# Antenna_analyzer_shield.net
KiCad netlist of a schematic drawn in EAGLE
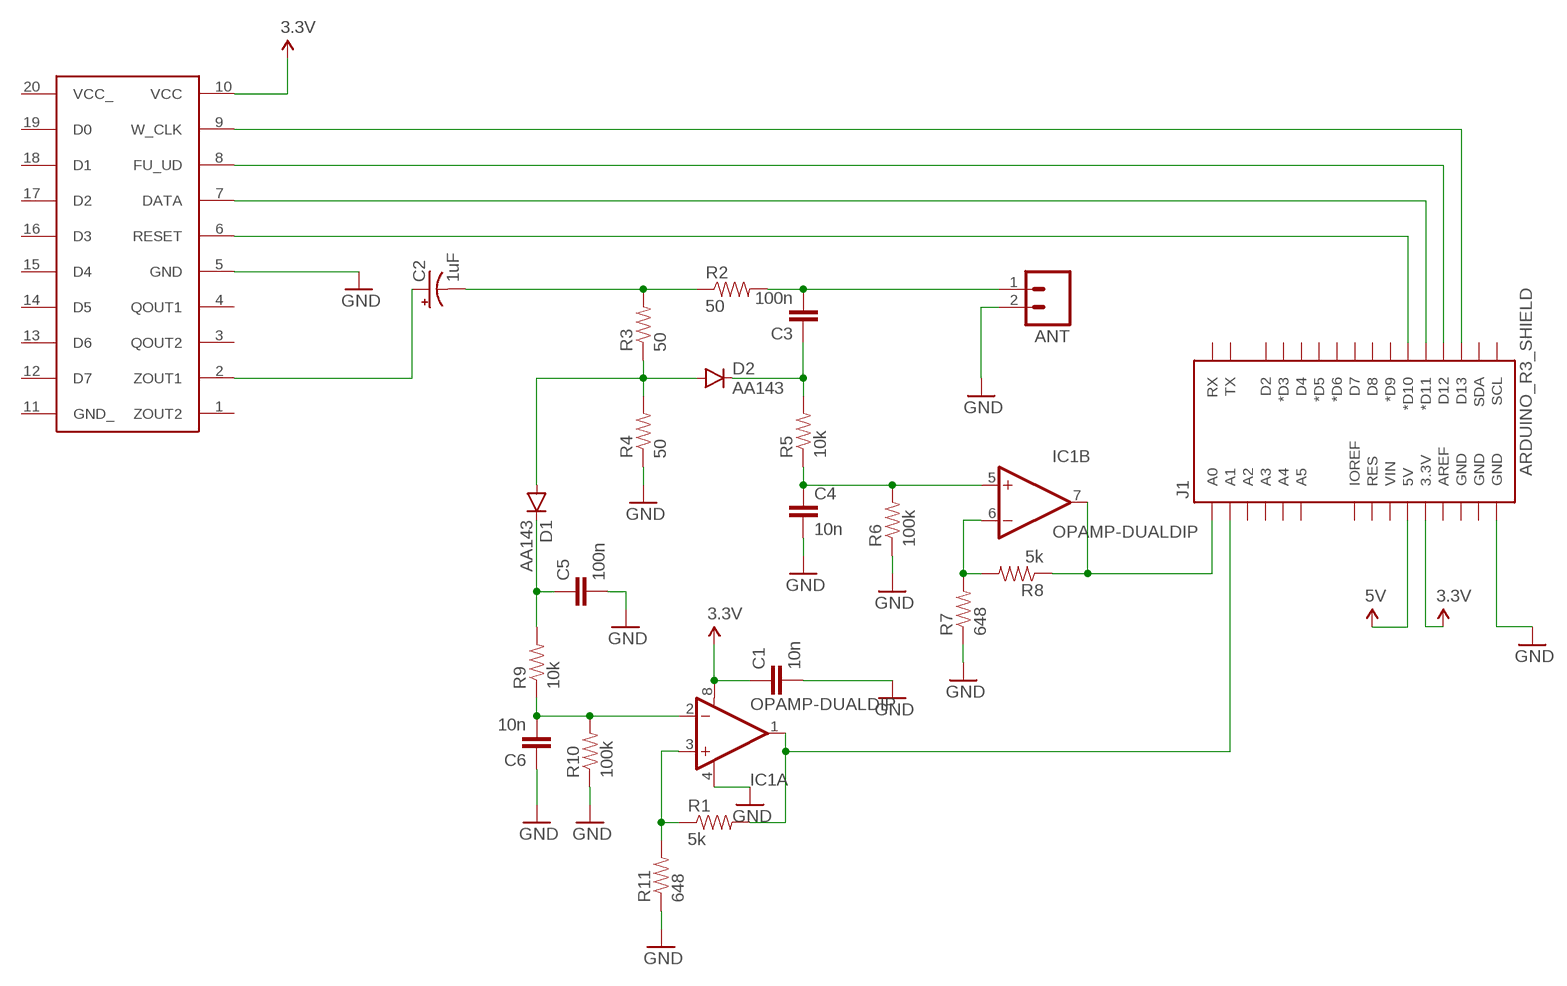
[diagram p0: schematic, sheet 1]

(export (version "E")
  (design (tool "Eeschema 10.0.6"))
  (components
    (comp (ref "ANT")
      (value "M023.5MM")
      (footprint "eagle-import:SCREWTERMINAL-3.5MM-2")
      (libsource (lib "eagle-import") (part "M023.5MM"))
    )
    (comp (ref "C1")
      (value "10n")
      (footprint "eagle-import:CAP-PTH-SMALL2")
      (libsource (lib "eagle-import") (part "CAPPTH2"))
    )
    (comp (ref "C2")
      (value "1uF")
      (footprint "eagle-import:CPOL-RADIAL-10UF-25V")
      (libsource (lib "eagle-import") (part "CAP_POLPTH2"))
    )
    (comp (ref "C3")
      (value "100n")
      (footprint "eagle-import:CAP-PTH-SMALL2")
      (libsource (lib "eagle-import") (part "CAPPTH2"))
    )
    (comp (ref "C4")
      (value "10n")
      (footprint "eagle-import:CAP-PTH-SMALL2")
      (libsource (lib "eagle-import") (part "CAPPTH2"))
    )
    (comp (ref "C5")
      (value "100n")
      (footprint "eagle-import:CAP-PTH-SMALL2")
      (libsource (lib "eagle-import") (part "CAPPTH2"))
    )
    (comp (ref "C6")
      (value "10n")
      (footprint "eagle-import:CAP-PTH-SMALL2")
      (libsource (lib "eagle-import") (part "CAPPTH2"))
    )
    (comp (ref "D1")
      (value "AA143")
      (footprint "eagle-import:DIODE-1N4001")
      (libsource (lib "eagle-import") (part "DIODEPTH"))
    )
    (comp (ref "D2")
      (value "AA143")
      (footprint "eagle-import:DIODE-1N4001")
      (libsource (lib "eagle-import") (part "DIODEPTH"))
    )
    (comp (ref "IC1")
      (value "OPAMP-DUALDIP")
      (footprint "eagle-import:DIP08")
      (libsource (lib "eagle-import") (part "OPAMP-DUALDIP"))
    )
    (comp (ref "J1")
      (value "ARDUINO_R3_SHIELD")
      (footprint "eagle-import:UNO_R3_SHIELD")
      (libsource (lib "eagle-import") (part "ARDUINO_R3_SHIELD"))
    )
    (comp (ref "R1")
      (value "5k")
      (footprint "eagle-import:AXIAL-0.4")
      (libsource (lib "eagle-import") (part "RESISTORPTH-1/4W"))
    )
    (comp (ref "R2")
      (value "50")
      (footprint "eagle-import:AXIAL-0.4")
      (libsource (lib "eagle-import") (part "RESISTORPTH-1/4W"))
    )
    (comp (ref "R3")
      (value "50")
      (footprint "eagle-import:AXIAL-0.4")
      (libsource (lib "eagle-import") (part "RESISTORPTH-1/4W"))
    )
    (comp (ref "R4")
      (value "50")
      (footprint "eagle-import:AXIAL-0.4")
      (libsource (lib "eagle-import") (part "RESISTORPTH-1/4W"))
    )
    (comp (ref "R5")
      (value "10k")
      (footprint "eagle-import:AXIAL-0.4")
      (libsource (lib "eagle-import") (part "RESISTORPTH-1/4W"))
    )
    (comp (ref "R6")
      (value "100k")
      (footprint "eagle-import:AXIAL-0.4")
      (libsource (lib "eagle-import") (part "RESISTORPTH-1/4W"))
    )
    (comp (ref "R7")
      (value "648")
      (footprint "eagle-import:AXIAL-0.4")
      (libsource (lib "eagle-import") (part "RESISTORPTH-1/4W"))
    )
    (comp (ref "R8")
      (value "5k")
      (footprint "eagle-import:AXIAL-0.4")
      (libsource (lib "eagle-import") (part "RESISTORPTH-1/4W"))
    )
    (comp (ref "R9")
      (value "10k")
      (footprint "eagle-import:AXIAL-0.4")
      (libsource (lib "eagle-import") (part "RESISTORPTH-1/4W"))
    )
    (comp (ref "R10")
      (value "100k")
      (footprint "eagle-import:AXIAL-0.4")
      (libsource (lib "eagle-import") (part "RESISTORPTH-1/4W"))
    )
    (comp (ref "R11")
      (value "648")
      (footprint "eagle-import:AXIAL-0.4")
      (libsource (lib "eagle-import") (part "RESISTORPTH-1/4W"))
    )
    (comp (ref "U$1")
      (value "DDS")
      (footprint "eagle-import:1X10_NO_SILK")
      (libsource (lib "eagle-import") (part "DDS"))
    )
  )
  (nets
    (net (code "1") (name "3.3V") (class "Default")
      (node (ref "C1") (pin "1") (pinfunction "1_1") (pintype "passive"))
      (node (ref "IC1") (pin "8") (pinfunction "V+_8") (pintype "power_in"))
      (node (ref "J1") (pin "3.3V") (pinfunction "3.3V_3.3V") (pintype "bidirectional"))
      (node (ref "J1") (pin "5V") (pinfunction "5V_5V") (pintype "bidirectional"))
      (node (ref "U$1") (pin "10") (pinfunction "VCC_10") (pintype "bidirectional"))
    )
    (net (code "2") (name "GND") (class "Default")
      (node (ref "ANT") (pin "2") (pinfunction "2_2") (pintype "passive"))
      (node (ref "C1") (pin "2") (pinfunction "2_2") (pintype "passive"))
      (node (ref "C4") (pin "2") (pinfunction "2_2") (pintype "passive"))
      (node (ref "C5") (pin "2") (pinfunction "2_2") (pintype "passive"))
      (node (ref "C6") (pin "1") (pinfunction "1_1") (pintype "passive"))
      (node (ref "IC1") (pin "4") (pinfunction "V-_4") (pintype "power_in"))
      (node (ref "J1") (pin "GND@0") (pinfunction "GND_GND@0") (pintype "bidirectional"))
      (node (ref "R10") (pin "P$1") (pinfunction "1_P$1") (pintype "passive"))
      (node (ref "R11") (pin "P$1") (pinfunction "1_P$1") (pintype "passive"))
      (node (ref "R4") (pin "P$1") (pinfunction "1_P$1") (pintype "passive"))
      (node (ref "R6") (pin "P$1") (pinfunction "1_P$1") (pintype "passive"))
      (node (ref "R7") (pin "P$1") (pinfunction "1_P$1") (pintype "passive"))
      (node (ref "U$1") (pin "5") (pinfunction "GND_5") (pintype "bidirectional"))
    )
    (net (code "3") (name "Net-(C2-+)") (class "Default")
      (node (ref "C2") (pin "1") (pinfunction "+_1") (pintype "passive"))
      (node (ref "U$1") (pin "2") (pinfunction "ZOUT1_2") (pintype "bidirectional"))
    )
    (net (code "4") (name "Net-(C2--)") (class "Default")
      (node (ref "C2") (pin "2") (pinfunction "-_2") (pintype "passive"))
      (node (ref "R2") (pin "P$1") (pinfunction "1_P$1") (pintype "passive"))
      (node (ref "R3") (pin "P$2") (pinfunction "2_P$2") (pintype "passive"))
    )
    (net (code "5") (name "Net-(IC1A-+IN)") (class "Default")
      (node (ref "IC1") (pin "3") (pinfunction "+IN_3") (pintype "input"))
      (node (ref "R1") (pin "P$1") (pinfunction "1_P$1") (pintype "passive"))
      (node (ref "R11") (pin "P$2") (pinfunction "2_P$2") (pintype "passive"))
    )
    (net (code "6") (name "Net-(IC1A--IN)") (class "Default")
      (node (ref "C6") (pin "2") (pinfunction "2_2") (pintype "passive"))
      (node (ref "IC1") (pin "2") (pinfunction "-IN_2") (pintype "input"))
      (node (ref "R10") (pin "P$2") (pinfunction "2_P$2") (pintype "passive"))
      (node (ref "R9") (pin "P$1") (pinfunction "1_P$1") (pintype "passive"))
    )
    (net (code "7") (name "Net-(IC1A-OUT)") (class "Default")
      (node (ref "IC1") (pin "1") (pinfunction "OUT_1") (pintype "output"))
      (node (ref "J1") (pin "A1") (pinfunction "A1_A1") (pintype "bidirectional"))
      (node (ref "R1") (pin "P$2") (pinfunction "2_P$2") (pintype "passive"))
    )
    (net (code "8") (name "Net-(IC1B-+IN)") (class "Default")
      (node (ref "C4") (pin "1") (pinfunction "1_1") (pintype "passive"))
      (node (ref "IC1") (pin "5") (pinfunction "+IN_5") (pintype "input"))
      (node (ref "R5") (pin "P$1") (pinfunction "1_P$1") (pintype "passive"))
      (node (ref "R6") (pin "P$2") (pinfunction "2_P$2") (pintype "passive"))
    )
    (net (code "9") (name "Net-(IC1B--IN)") (class "Default")
      (node (ref "IC1") (pin "6") (pinfunction "-IN_6") (pintype "input"))
      (node (ref "R7") (pin "P$2") (pinfunction "2_P$2") (pintype "passive"))
      (node (ref "R8") (pin "P$2") (pinfunction "2_P$2") (pintype "passive"))
    )
    (net (code "10") (name "Net-(IC1B-OUT)") (class "Default")
      (node (ref "IC1") (pin "7") (pinfunction "OUT_7") (pintype "output"))
      (node (ref "J1") (pin "A0") (pinfunction "A0_A0") (pintype "bidirectional"))
      (node (ref "R8") (pin "P$1") (pinfunction "1_P$1") (pintype "passive"))
    )
    (net (code "11") (name "Net-(J1-*D10)") (class "Default")
      (node (ref "J1") (pin "D10") (pinfunction "*D10_D10") (pintype "bidirectional"))
      (node (ref "U$1") (pin "6") (pinfunction "RESET_6") (pintype "bidirectional"))
    )
    (net (code "12") (name "Net-(J1-*D11)") (class "Default")
      (node (ref "J1") (pin "D11") (pinfunction "*D11_D11") (pintype "bidirectional"))
      (node (ref "U$1") (pin "7") (pinfunction "DATA_7") (pintype "bidirectional"))
    )
    (net (code "13") (name "Net-(R2-2)") (class "Default")
      (node (ref "ANT") (pin "1") (pinfunction "1_1") (pintype "passive"))
      (node (ref "C3") (pin "2") (pinfunction "2_2") (pintype "passive"))
      (node (ref "R2") (pin "P$2") (pinfunction "2_P$2") (pintype "passive"))
    )
    (net (code "14") (name "Net-(R3-1)") (class "Default")
      (node (ref "D1") (pin "A") (pinfunction "A_A") (pintype "passive"))
      (node (ref "D2") (pin "A") (pinfunction "A_A") (pintype "passive"))
      (node (ref "R3") (pin "P$1") (pinfunction "1_P$1") (pintype "passive"))
      (node (ref "R4") (pin "P$2") (pinfunction "2_P$2") (pintype "passive"))
    )
    (net (code "15") (name "Net-(R5-2)") (class "Default")
      (node (ref "C3") (pin "1") (pinfunction "1_1") (pintype "passive"))
      (node (ref "D2") (pin "C") (pinfunction "C_C") (pintype "passive"))
      (node (ref "R5") (pin "P$2") (pinfunction "2_P$2") (pintype "passive"))
    )
    (net (code "16") (name "Net-(R9-2)") (class "Default")
      (node (ref "C5") (pin "1") (pinfunction "1_1") (pintype "passive"))
      (node (ref "D1") (pin "C") (pinfunction "C_C") (pintype "passive"))
      (node (ref "R9") (pin "P$2") (pinfunction "2_P$2") (pintype "passive"))
    )
    (net (code "17") (name "Net-(U$1-FU_UD)") (class "Default")
      (node (ref "J1") (pin "D12") (pinfunction "D12_D12") (pintype "bidirectional"))
      (node (ref "U$1") (pin "8") (pinfunction "FU_UD_8") (pintype "bidirectional"))
    )
    (net (code "18") (name "Net-(U$1-W_CLK)") (class "Default")
      (node (ref "J1") (pin "D13") (pinfunction "D13_D13") (pintype "bidirectional"))
      (node (ref "U$1") (pin "9") (pinfunction "W_CLK_9") (pintype "bidirectional"))
    )
    (net (code "19") (name "unconnected-(J1-*D3-PadD3)") (class "Default")
      (node (ref "J1") (pin "D3") (pinfunction "*D3_D3") (pintype "bidirectional"))
    )
    (net (code "20") (name "unconnected-(J1-*D5-PadD5)") (class "Default")
      (node (ref "J1") (pin "D5") (pinfunction "*D5_D5") (pintype "bidirectional"))
    )
    (net (code "21") (name "unconnected-(J1-*D6-PadD6)") (class "Default")
      (node (ref "J1") (pin "D6") (pinfunction "*D6_D6") (pintype "bidirectional"))
    )
    (net (code "22") (name "unconnected-(J1-*D9-PadD9)") (class "Default")
      (node (ref "J1") (pin "D9") (pinfunction "*D9_D9") (pintype "bidirectional"))
    )
    (net (code "23") (name "unconnected-(J1-GND-PadGND@1)") (class "Default")
      (node (ref "J1") (pin "GND@1") (pinfunction "GND_GND@1") (pintype "bidirectional"))
    )
    (net (code "24") (name "unconnected-(J1-GND-PadGND@2)") (class "Default")
      (node (ref "J1") (pin "GND@2") (pinfunction "GND_GND@2") (pintype "bidirectional"))
    )
    (net (code "25") (name "unconnected-(J1-PadA2)") (class "Default")
      (node (ref "J1") (pin "A2") (pinfunction "A2_A2") (pintype "bidirectional"))
    )
    (net (code "26") (name "unconnected-(J1-PadA3)") (class "Default")
      (node (ref "J1") (pin "A3") (pinfunction "A3_A3") (pintype "bidirectional"))
    )
    (net (code "27") (name "unconnected-(J1-PadA4)") (class "Default")
      (node (ref "J1") (pin "A4") (pinfunction "A4_A4") (pintype "bidirectional"))
    )
    (net (code "28") (name "unconnected-(J1-PadA5)") (class "Default")
      (node (ref "J1") (pin "A5") (pinfunction "A5_A5") (pintype "bidirectional"))
    )
    (net (code "29") (name "unconnected-(J1-PadAREF)") (class "Default")
      (node (ref "J1") (pin "AREF") (pinfunction "AREF_AREF") (pintype "bidirectional"))
    )
    (net (code "30") (name "unconnected-(J1-PadD2)") (class "Default")
      (node (ref "J1") (pin "D2") (pinfunction "D2_D2") (pintype "bidirectional"))
    )
    (net (code "31") (name "unconnected-(J1-PadD4)") (class "Default")
      (node (ref "J1") (pin "D4") (pinfunction "D4_D4") (pintype "bidirectional"))
    )
    (net (code "32") (name "unconnected-(J1-PadD7)") (class "Default")
      (node (ref "J1") (pin "D7") (pinfunction "D7_D7") (pintype "bidirectional"))
    )
    (net (code "33") (name "unconnected-(J1-PadD8)") (class "Default")
      (node (ref "J1") (pin "D8") (pinfunction "D8_D8") (pintype "bidirectional"))
    )
    (net (code "34") (name "unconnected-(J1-PadIOREF)") (class "Default")
      (node (ref "J1") (pin "IOREF") (pinfunction "IOREF_IOREF") (pintype "bidirectional"))
    )
    (net (code "35") (name "unconnected-(J1-PadRES)") (class "Default")
      (node (ref "J1") (pin "RES") (pinfunction "RES_RES") (pintype "bidirectional"))
    )
    (net (code "36") (name "unconnected-(J1-PadRX)") (class "Default")
      (node (ref "J1") (pin "RX") (pinfunction "RX_RX") (pintype "bidirectional"))
    )
    (net (code "37") (name "unconnected-(J1-PadSCL)") (class "Default")
      (node (ref "J1") (pin "SCL") (pinfunction "SCL_SCL") (pintype "bidirectional"))
    )
    (net (code "38") (name "unconnected-(J1-PadSDA)") (class "Default")
      (node (ref "J1") (pin "SDA") (pinfunction "SDA_SDA") (pintype "bidirectional"))
    )
    (net (code "39") (name "unconnected-(J1-PadTX)") (class "Default")
      (node (ref "J1") (pin "TX") (pinfunction "TX_TX") (pintype "bidirectional"))
    )
    (net (code "40") (name "unconnected-(J1-PadVIN)") (class "Default")
      (node (ref "J1") (pin "VIN") (pinfunction "VIN_VIN") (pintype "bidirectional"))
    )
    (net (code "41") (name "unconnected-(U$1-D0-Pad19)") (class "Default")
      (node (ref "U$1") (pin "19") (pinfunction "D0_19") (pintype "bidirectional"))
    )
    (net (code "42") (name "unconnected-(U$1-D1-Pad18)") (class "Default")
      (node (ref "U$1") (pin "18") (pinfunction "D1_18") (pintype "bidirectional"))
    )
    (net (code "43") (name "unconnected-(U$1-D2-Pad17)") (class "Default")
      (node (ref "U$1") (pin "17") (pinfunction "D2_17") (pintype "bidirectional"))
    )
    (net (code "44") (name "unconnected-(U$1-D3-Pad16)") (class "Default")
      (node (ref "U$1") (pin "16") (pinfunction "D3_16") (pintype "bidirectional"))
    )
    (net (code "45") (name "unconnected-(U$1-D4-Pad15)") (class "Default")
      (node (ref "U$1") (pin "15") (pinfunction "D4_15") (pintype "bidirectional"))
    )
    (net (code "46") (name "unconnected-(U$1-D5-Pad14)") (class "Default")
      (node (ref "U$1") (pin "14") (pinfunction "D5_14") (pintype "bidirectional"))
    )
    (net (code "47") (name "unconnected-(U$1-D6-Pad13)") (class "Default")
      (node (ref "U$1") (pin "13") (pinfunction "D6_13") (pintype "bidirectional"))
    )
    (net (code "48") (name "unconnected-(U$1-D7-Pad12)") (class "Default")
      (node (ref "U$1") (pin "12") (pinfunction "D7_12") (pintype "bidirectional"))
    )
    (net (code "49") (name "unconnected-(U$1-GND_-Pad11)") (class "Default")
      (node (ref "U$1") (pin "11") (pinfunction "GND__11") (pintype "bidirectional"))
    )
    (net (code "50") (name "unconnected-(U$1-QOUT1-Pad4)") (class "Default")
      (node (ref "U$1") (pin "4") (pinfunction "QOUT1_4") (pintype "bidirectional"))
    )
    (net (code "51") (name "unconnected-(U$1-QOUT2-Pad3)") (class "Default")
      (node (ref "U$1") (pin "3") (pinfunction "QOUT2_3") (pintype "bidirectional"))
    )
    (net (code "52") (name "unconnected-(U$1-VCC_-Pad20)") (class "Default")
      (node (ref "U$1") (pin "20") (pinfunction "VCC__20") (pintype "bidirectional"))
    )
    (net (code "53") (name "unconnected-(U$1-ZOUT2-Pad1)") (class "Default")
      (node (ref "U$1") (pin "1") (pinfunction "ZOUT2_1") (pintype "bidirectional"))
    )
  )
)
